# interface_ntc10k.net
KiCad netlist of a schematic drawn in Altium Designer
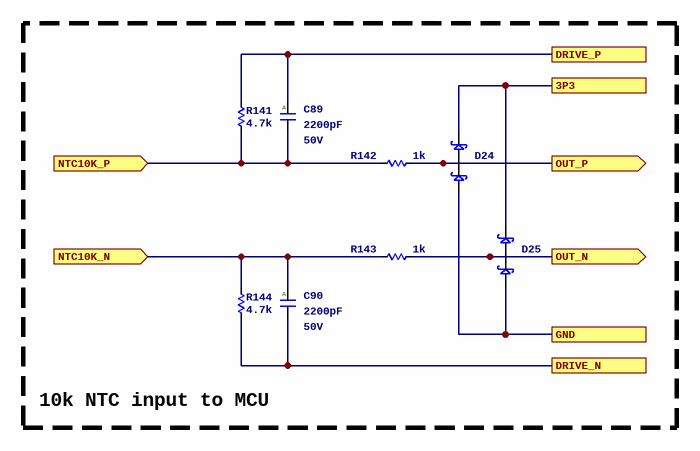
[diagram p0: interface_ntc10k.SchDoc]

(export (version "E")
  (design (tool "Eeschema 10.0.6"))
  (components
    (comp (ref "C89")
      (value "CGA2B2X7R1H222M050BA")
      (footprint "C0402_0.55MM")
      (description "CAP CER 2200PF 50V X7R 0402")
      (fields
        (field (name "CAPACITANCE") "2200pF")
        (field (name "VOLTAGE - RATED") "50V")
        (field (name "TOLERANCE") "±20%")
        (field (name "MANUFACTURER") "TDK Corporation")
      )
      (libsource (lib "sscp") (part "__template_cap_auto"))
    )
    (comp (ref "C90")
      (value "CGA2B2X7R1H222M050BA")
      (footprint "C0402_0.55MM")
      (description "CAP CER 2200PF 50V X7R 0402")
      (fields
        (field (name "CAPACITANCE") "2200pF")
        (field (name "VOLTAGE - RATED") "50V")
        (field (name "TOLERANCE") "±20%")
        (field (name "MANUFACTURER") "TDK Corporation")
      )
      (libsource (lib "sscp") (part "__template_cap_auto"))
    )
    (comp (ref "D24")
      (value "BAT54SLT1G")
      (footprint "3SOT23")
      (description "DIODE SCHOTTKY DUAL 30V SOT23")
      (fields (field (name "MANUFACTURER") "ON Semiconductor"))
      (libsource (lib "SSCP") (part "SCHOTTKY_30V_DUAL_BAT54SLT1G"))
    )
    (comp (ref "D25")
      (value "BAT54SLT1G")
      (footprint "3SOT23")
      (description "DIODE SCHOTTKY DUAL 30V SOT23")
      (fields (field (name "MANUFACTURER") "ON Semiconductor"))
      (libsource (lib "SSCP") (part "SCHOTTKY_30V_DUAL_BAT54SLT1G"))
    )
    (comp (ref "R141")
      (value "ERJ-2RKF4701X")
      (footprint "R0402_0.40MM")
      (description "RES SMD 4.7K OHM 1% 1/10W 0402")
      (fields
        (field (name "RESISTANCE") "4.7k")
        (field (name "TOLERANCE") "±1%")
        (field (name "MANUFACTURER") "Panasonic Electronic Components")
      )
      (libsource (lib "sscp") (part "__template_resistor"))
    )
    (comp (ref "R142")
      (value "~")
      (footprint "R0402_0.40MM")
      (description "RES SMD 1K OHM 1% 1/10W 0402")
      (fields (field (name "RESISTANCE") "1k") (field (name "TOLERANCE") "±1%"))
      (libsource (lib "sscp") (part "__template_resistor"))
    )
    (comp (ref "R143")
      (value "~")
      (footprint "R0402_0.40MM")
      (description "RES SMD 1K OHM 1% 1/10W 0402")
      (fields (field (name "RESISTANCE") "1k") (field (name "TOLERANCE") "±1%"))
      (libsource (lib "sscp") (part "__template_resistor"))
    )
    (comp (ref "R144")
      (value "ERJ-2RKF4701X")
      (footprint "R0402_0.40MM")
      (description "RES SMD 4.7K OHM 1% 1/10W 0402")
      (fields
        (field (name "RESISTANCE") "4.7k")
        (field (name "TOLERANCE") "±1%")
        (field (name "MANUFACTURER") "Panasonic Electronic Components")
      )
      (libsource (lib "sscp") (part "__template_resistor"))
    )
  )
  (nets
    (net (code "1") (name "/3P3") (class "Default")
      (node (ref "D24") (pin "2") (pintype "passive"))
      (node (ref "D25") (pin "2") (pintype "passive"))
    )
    (net (code "2") (name "/DRIVE_N") (class "Default")
      (node (ref "C90") (pin "2") (pintype "passive"))
      (node (ref "R144") (pin "2") (pintype "passive"))
    )
    (net (code "3") (name "/DRIVE_P") (class "Default")
      (node (ref "C89") (pin "1") (pintype "passive"))
      (node (ref "R141") (pin "1") (pintype "passive"))
    )
    (net (code "4") (name "/GND") (class "Default")
      (node (ref "D24") (pin "1") (pintype "passive"))
      (node (ref "D25") (pin "1") (pintype "passive"))
    )
    (net (code "5") (name "/NTC10K_N") (class "Default")
      (node (ref "C90") (pin "1") (pintype "passive"))
      (node (ref "R143") (pin "1") (pintype "passive"))
      (node (ref "R144") (pin "1") (pintype "passive"))
    )
    (net (code "6") (name "/NTC10K_P") (class "Default")
      (node (ref "C89") (pin "2") (pintype "passive"))
      (node (ref "R141") (pin "2") (pintype "passive"))
      (node (ref "R142") (pin "1") (pintype "passive"))
    )
    (net (code "7") (name "/OUT_N") (class "Default")
      (node (ref "D25") (pin "3") (pintype "passive"))
      (node (ref "R143") (pin "2") (pintype "passive"))
    )
    (net (code "8") (name "/OUT_P") (class "Default")
      (node (ref "D24") (pin "3") (pintype "passive"))
      (node (ref "R142") (pin "2") (pintype "passive"))
    )
  )
)
